# Netzteil-Regler.net
KiCad netlist of a schematic drawn in EAGLE
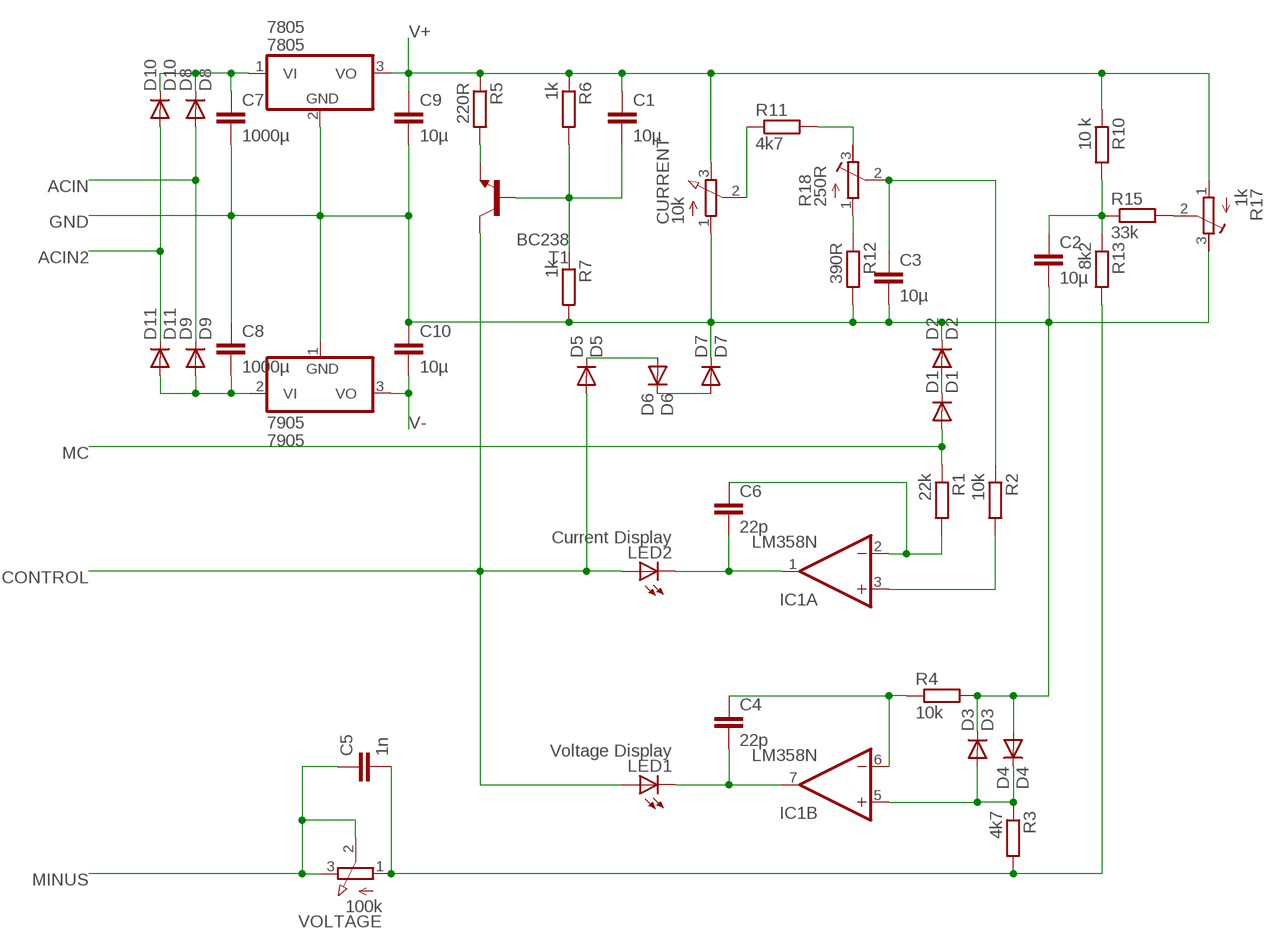
[diagram p0: schematic, sheet 1]

(export (version "E")
  (design (tool "Eeschema 10.0.6"))
  (components
    (comp (ref "7805")
      (value "7805")
      (footprint "eagle-import:TO220V")
      (libsource (lib "eagle-import") (part "78TV05"))
    )
    (comp (ref "7905")
      (value "7905")
      (footprint "eagle-import:TO220V")
      (libsource (lib "eagle-import") (part "MC79MT05C"))
    )
    (comp (ref "C1")
      (value "10µ")
      (footprint "eagle-import:C2.5-5")
      (libsource (lib "eagle-import") (part "C2.5/5"))
    )
    (comp (ref "C2")
      (value "10µ")
      (footprint "eagle-import:C2.5-5")
      (libsource (lib "eagle-import") (part "C2.5/5"))
    )
    (comp (ref "C3")
      (value "10µ")
      (footprint "eagle-import:C2.5-5")
      (libsource (lib "eagle-import") (part "C2.5/5"))
    )
    (comp (ref "C4")
      (value "22p")
      (footprint "eagle-import:C5B4.5")
      (libsource (lib "eagle-import") (part "C5/4.5"))
    )
    (comp (ref "C5")
      (value "1n")
      (footprint "eagle-import:C5B4.5")
      (libsource (lib "eagle-import") (part "C5/4.5"))
    )
    (comp (ref "C6")
      (value "22p")
      (footprint "eagle-import:C5B4.5")
      (libsource (lib "eagle-import") (part "C5/4.5"))
    )
    (comp (ref "C7")
      (value "1000µ")
      (footprint "eagle-import:C10B6")
      (libsource (lib "eagle-import") (part "C10/6"))
    )
    (comp (ref "C8")
      (value "1000µ")
      (footprint "eagle-import:C10B6")
      (libsource (lib "eagle-import") (part "C10/6"))
    )
    (comp (ref "C9")
      (value "10µ")
      (footprint "eagle-import:C2.5-5")
      (libsource (lib "eagle-import") (part "C2.5/5"))
    )
    (comp (ref "C10")
      (value "10µ")
      (footprint "eagle-import:C2.5-5")
      (libsource (lib "eagle-import") (part "C2.5/5"))
    )
    (comp (ref "CURRENT")
      (value "10k")
      (footprint "eagle-import:3RP_1610N")
      (libsource (lib "eagle-import") (part "3RP/1610N"))
    )
    (comp (ref "D1")
      (value "D1")
      (footprint "eagle-import:DO35-10")
      (libsource (lib "eagle-import") (part "1N4148DO35-10"))
    )
    (comp (ref "D2")
      (value "D2")
      (footprint "eagle-import:DO35-10")
      (libsource (lib "eagle-import") (part "1N4148DO35-10"))
    )
    (comp (ref "D3")
      (value "D3")
      (footprint "eagle-import:DO35-10")
      (libsource (lib "eagle-import") (part "1N4148DO35-10"))
    )
    (comp (ref "D4")
      (value "D4")
      (footprint "eagle-import:DO35-10")
      (libsource (lib "eagle-import") (part "1N4148DO35-10"))
    )
    (comp (ref "D5")
      (value "D5")
      (footprint "eagle-import:DO35-10")
      (libsource (lib "eagle-import") (part "1N4148DO35-10"))
    )
    (comp (ref "D6")
      (value "D6")
      (footprint "eagle-import:DO35-10")
      (libsource (lib "eagle-import") (part "1N4148DO35-10"))
    )
    (comp (ref "D7")
      (value "D7")
      (footprint "eagle-import:DO35-10")
      (libsource (lib "eagle-import") (part "1N4148DO35-10"))
    )
    (comp (ref "D8")
      (value "D8")
      (footprint "eagle-import:DO41-10")
      (libsource (lib "eagle-import") (part "1N4004"))
    )
    (comp (ref "D9")
      (value "D9")
      (footprint "eagle-import:DO41-10")
      (libsource (lib "eagle-import") (part "1N4004"))
    )
    (comp (ref "D10")
      (value "D10")
      (footprint "eagle-import:DO41-10")
      (libsource (lib "eagle-import") (part "1N4004"))
    )
    (comp (ref "D11")
      (value "D11")
      (footprint "eagle-import:DO41-10")
      (libsource (lib "eagle-import") (part "1N4004"))
    )
    (comp (ref "IC1")
      (value "LM358N")
      (footprint "eagle-import:DIL08")
      (libsource (lib "eagle-import") (part "LM358N"))
    )
    (comp (ref "LED1")
      (value "Voltage Display")
      (footprint "eagle-import:LED5MM")
      (libsource (lib "eagle-import") (part "LED5MM"))
    )
    (comp (ref "LED2")
      (value "Current Display")
      (footprint "eagle-import:LED5MM")
      (libsource (lib "eagle-import") (part "LED5MM"))
    )
    (comp (ref "R1")
      (value "22k")
      (footprint "eagle-import:0207_10")
      (libsource (lib "eagle-import") (part "R-EU_0207/10"))
    )
    (comp (ref "R2")
      (value "10k")
      (footprint "eagle-import:0207_10")
      (libsource (lib "eagle-import") (part "R-EU_0207/10"))
    )
    (comp (ref "R3")
      (value "4k7")
      (footprint "eagle-import:0207_10")
      (libsource (lib "eagle-import") (part "R-EU_0207/10"))
    )
    (comp (ref "R4")
      (value "10k")
      (footprint "eagle-import:0207_10")
      (libsource (lib "eagle-import") (part "R-EU_0207/10"))
    )
    (comp (ref "R5")
      (value "220R")
      (footprint "eagle-import:0207_10")
      (libsource (lib "eagle-import") (part "R-EU_0207/10"))
    )
    (comp (ref "R6")
      (value "1k")
      (footprint "eagle-import:0207_10")
      (libsource (lib "eagle-import") (part "R-EU_0207/10"))
    )
    (comp (ref "R7")
      (value "1k")
      (footprint "eagle-import:0207_10")
      (libsource (lib "eagle-import") (part "R-EU_0207/10"))
    )
    (comp (ref "R10")
      (value "10 k")
      (footprint "eagle-import:0207_10")
      (libsource (lib "eagle-import") (part "R-EU_0207/10"))
    )
    (comp (ref "R11")
      (value "4k7")
      (footprint "eagle-import:0207_10")
      (libsource (lib "eagle-import") (part "R-EU_0207/10"))
    )
    (comp (ref "R12")
      (value "390R")
      (footprint "eagle-import:0207_10")
      (libsource (lib "eagle-import") (part "R-EU_0207/10"))
    )
    (comp (ref "R13")
      (value "8k2")
      (footprint "eagle-import:0207_10")
      (libsource (lib "eagle-import") (part "R-EU_0207/10"))
    )
    (comp (ref "R15")
      (value "33k")
      (footprint "eagle-import:0207_10")
      (libsource (lib "eagle-import") (part "R-EU_0207/10"))
    )
    (comp (ref "R17")
      (value "1k")
      (footprint "eagle-import:RTRIM3296W")
      (libsource (lib "eagle-import") (part "R-TRIMM3296W"))
    )
    (comp (ref "R18")
      (value "250R")
      (footprint "eagle-import:RTRIM3296W")
      (libsource (lib "eagle-import") (part "R-TRIMM3296W"))
    )
    (comp (ref "T1")
      (value "BC238")
      (footprint "eagle-import:TO92-CBE")
      (libsource (lib "eagle-import") (part "-NPN-TO92-CBEBC238"))
    )
    (comp (ref "VOLTAGE")
      (value "100k")
      (footprint "eagle-import:3RP_1610N")
      (libsource (lib "eagle-import") (part "3RP/1610N"))
    )
  )
  (nets
    (net (code "1") (name "/ACIN") (class "Default")
      (node (ref "D8") (pin "A") (pinfunction "A_A") (pintype "passive"))
      (node (ref "D9") (pin "C") (pinfunction "C_C") (pintype "passive"))
    )
    (net (code "2") (name "/ACIN2") (class "Default")
      (node (ref "D10") (pin "A") (pinfunction "A_A") (pintype "passive"))
      (node (ref "D11") (pin "C") (pinfunction "C_C") (pintype "passive"))
    )
    (net (code "3") (name "/CONTROL") (class "Default")
      (node (ref "D5") (pin "A") (pinfunction "A_A") (pintype "passive"))
      (node (ref "LED1") (pin "A") (pinfunction "A_A") (pintype "passive"))
      (node (ref "LED2") (pin "A") (pinfunction "A_A") (pintype "passive"))
      (node (ref "T1") (pin "C") (pinfunction "C_C") (pintype "passive"))
    )
    (net (code "4") (name "/GND") (class "Default")
      (node (ref "7805") (pin "2") (pinfunction "GND_2") (pintype "passive"))
      (node (ref "7905") (pin "1") (pinfunction "GND_1") (pintype "passive"))
      (node (ref "C10") (pin "1") (pinfunction "1_1") (pintype "passive"))
      (node (ref "C2") (pin "2") (pinfunction "2_2") (pintype "passive"))
      (node (ref "C3") (pin "2") (pinfunction "2_2") (pintype "passive"))
      (node (ref "C7") (pin "2") (pinfunction "2_2") (pintype "passive"))
      (node (ref "C8") (pin "1") (pinfunction "1_1") (pintype "passive"))
      (node (ref "C9") (pin "2") (pinfunction "2_2") (pintype "passive"))
      (node (ref "CURRENT") (pin "1") (pinfunction "A_1") (pintype "passive"))
      (node (ref "D2") (pin "C") (pinfunction "C_C") (pintype "passive"))
      (node (ref "D3") (pin "C") (pinfunction "C_C") (pintype "passive"))
      (node (ref "D4") (pin "A") (pinfunction "A_A") (pintype "passive"))
      (node (ref "D7") (pin "C") (pinfunction "C_C") (pintype "passive"))
      (node (ref "R12") (pin "2") (pinfunction "2_2") (pintype "passive"))
      (node (ref "R17") (pin "3") (pinfunction "A_3") (pintype "passive"))
      (node (ref "R4") (pin "2") (pinfunction "2_2") (pintype "passive"))
      (node (ref "R7") (pin "2") (pinfunction "2_2") (pintype "passive"))
    )
    (net (code "5") (name "/MC") (class "Default")
      (node (ref "D1") (pin "A") (pinfunction "A_A") (pintype "passive"))
      (node (ref "R1") (pin "1") (pinfunction "1_1") (pintype "passive"))
    )
    (net (code "6") (name "/MINUS") (class "Default")
      (node (ref "C5") (pin "1") (pinfunction "1_1") (pintype "passive"))
      (node (ref "VOLTAGE") (pin "2") (pinfunction "S_2") (pintype "passive"))
      (node (ref "VOLTAGE") (pin "3") (pinfunction "E_3") (pintype "passive"))
    )
    (net (code "7") (name "/V+") (class "Default")
      (node (ref "7805") (pin "3") (pinfunction "VO_3") (pintype "passive"))
      (node (ref "C1") (pin "1") (pinfunction "1_1") (pintype "passive"))
      (node (ref "C9") (pin "1") (pinfunction "1_1") (pintype "passive"))
      (node (ref "CURRENT") (pin "3") (pinfunction "E_3") (pintype "passive"))
      (node (ref "R10") (pin "1") (pinfunction "1_1") (pintype "passive"))
      (node (ref "R17") (pin "1") (pinfunction "E_1") (pintype "passive"))
      (node (ref "R5") (pin "1") (pinfunction "1_1") (pintype "passive"))
      (node (ref "R6") (pin "1") (pinfunction "1_1") (pintype "passive"))
    )
    (net (code "8") (name "/V-") (class "Default")
      (node (ref "7905") (pin "3") (pinfunction "VO_3") (pintype "passive"))
      (node (ref "C10") (pin "2") (pinfunction "2_2") (pintype "passive"))
    )
    (net (code "9") (name "Net-(7805-VI)") (class "Default")
      (node (ref "7805") (pin "1") (pinfunction "VI_1") (pintype "input"))
      (node (ref "C7") (pin "1") (pinfunction "1_1") (pintype "passive"))
      (node (ref "D10") (pin "C") (pinfunction "C_C") (pintype "passive"))
      (node (ref "D8") (pin "C") (pinfunction "C_C") (pintype "passive"))
    )
    (net (code "10") (name "Net-(7905-VI)") (class "Default")
      (node (ref "7905") (pin "2") (pinfunction "VI_2") (pintype "input"))
      (node (ref "C8") (pin "2") (pinfunction "2_2") (pintype "passive"))
      (node (ref "D11") (pin "A") (pinfunction "A_A") (pintype "passive"))
      (node (ref "D9") (pin "A") (pinfunction "A_A") (pintype "passive"))
    )
    (net (code "11") (name "Net-(C1-Pad2)") (class "Default")
      (node (ref "C1") (pin "2") (pinfunction "2_2") (pintype "passive"))
      (node (ref "R6") (pin "2") (pinfunction "2_2") (pintype "passive"))
      (node (ref "R7") (pin "1") (pinfunction "1_1") (pintype "passive"))
      (node (ref "T1") (pin "B") (pinfunction "B_B") (pintype "passive"))
    )
    (net (code "12") (name "Net-(C2-Pad1)") (class "Default")
      (node (ref "C2") (pin "1") (pinfunction "1_1") (pintype "passive"))
      (node (ref "R10") (pin "2") (pinfunction "2_2") (pintype "passive"))
      (node (ref "R13") (pin "1") (pinfunction "1_1") (pintype "passive"))
      (node (ref "R15") (pin "1") (pinfunction "1_1") (pintype "passive"))
    )
    (net (code "13") (name "Net-(CURRENT-S)") (class "Default")
      (node (ref "CURRENT") (pin "2") (pinfunction "S_2") (pintype "passive"))
      (node (ref "R11") (pin "1") (pinfunction "1_1") (pintype "passive"))
    )
    (net (code "14") (name "Net-(D1-PadC)") (class "Default")
      (node (ref "D1") (pin "C") (pinfunction "C_C") (pintype "passive"))
      (node (ref "D2") (pin "A") (pinfunction "A_A") (pintype "passive"))
    )
    (net (code "15") (name "Net-(D5-PadC)") (class "Default")
      (node (ref "D5") (pin "C") (pinfunction "C_C") (pintype "passive"))
      (node (ref "D6") (pin "A") (pinfunction "A_A") (pintype "passive"))
    )
    (net (code "16") (name "Net-(D6-PadC)") (class "Default")
      (node (ref "D6") (pin "C") (pinfunction "C_C") (pintype "passive"))
      (node (ref "D7") (pin "A") (pinfunction "A_A") (pintype "passive"))
    )
    (net (code "17") (name "Net-(IC1A-+IN)") (class "Default")
      (node (ref "IC1") (pin "3") (pinfunction "+IN_3") (pintype "input"))
      (node (ref "R2") (pin "2") (pinfunction "2_2") (pintype "passive"))
    )
    (net (code "18") (name "Net-(IC1A--IN)") (class "Default")
      (node (ref "C6") (pin "1") (pinfunction "1_1") (pintype "passive"))
      (node (ref "IC1") (pin "2") (pinfunction "-IN_2") (pintype "input"))
      (node (ref "R1") (pin "2") (pinfunction "2_2") (pintype "passive"))
    )
    (net (code "19") (name "Net-(IC1A-OUT)") (class "Default")
      (node (ref "C6") (pin "2") (pinfunction "2_2") (pintype "passive"))
      (node (ref "IC1") (pin "1") (pinfunction "OUT_1") (pintype "output"))
      (node (ref "LED2") (pin "K") (pinfunction "C_K") (pintype "passive"))
    )
    (net (code "20") (name "Net-(IC1B-+IN)") (class "Default")
      (node (ref "D3") (pin "A") (pinfunction "A_A") (pintype "passive"))
      (node (ref "D4") (pin "C") (pinfunction "C_C") (pintype "passive"))
      (node (ref "IC1") (pin "5") (pinfunction "+IN_5") (pintype "input"))
      (node (ref "R3") (pin "1") (pinfunction "1_1") (pintype "passive"))
    )
    (net (code "21") (name "Net-(IC1B--IN)") (class "Default")
      (node (ref "C4") (pin "1") (pinfunction "1_1") (pintype "passive"))
      (node (ref "IC1") (pin "6") (pinfunction "-IN_6") (pintype "input"))
      (node (ref "R4") (pin "1") (pinfunction "1_1") (pintype "passive"))
    )
    (net (code "22") (name "Net-(IC1B-OUT)") (class "Default")
      (node (ref "C4") (pin "2") (pinfunction "2_2") (pintype "passive"))
      (node (ref "IC1") (pin "7") (pinfunction "OUT_7") (pintype "output"))
      (node (ref "LED1") (pin "K") (pinfunction "C_K") (pintype "passive"))
    )
    (net (code "23") (name "Net-(R5-Pad2)") (class "Default")
      (node (ref "R5") (pin "2") (pinfunction "2_2") (pintype "passive"))
      (node (ref "T1") (pin "E") (pinfunction "E_E") (pintype "passive"))
    )
    (net (code "24") (name "Net-(R17-S)") (class "Default")
      (node (ref "R15") (pin "2") (pinfunction "2_2") (pintype "passive"))
      (node (ref "R17") (pin "2") (pinfunction "S_2") (pintype "passive"))
    )
    (net (code "25") (name "Net-(R18-A)") (class "Default")
      (node (ref "R11") (pin "2") (pinfunction "2_2") (pintype "passive"))
      (node (ref "R18") (pin "3") (pinfunction "A_3") (pintype "passive"))
    )
    (net (code "26") (name "Net-(R18-E)") (class "Default")
      (node (ref "R12") (pin "1") (pinfunction "1_1") (pintype "passive"))
      (node (ref "R18") (pin "1") (pinfunction "E_1") (pintype "passive"))
    )
    (net (code "27") (name "Net-(R18-S)") (class "Default")
      (node (ref "C3") (pin "1") (pinfunction "1_1") (pintype "passive"))
      (node (ref "R18") (pin "2") (pinfunction "S_2") (pintype "passive"))
      (node (ref "R2") (pin "1") (pinfunction "1_1") (pintype "passive"))
    )
    (net (code "28") (name "Net-(VOLTAGE-A)") (class "Default")
      (node (ref "C5") (pin "2") (pinfunction "2_2") (pintype "passive"))
      (node (ref "R13") (pin "2") (pinfunction "2_2") (pintype "passive"))
      (node (ref "R3") (pin "2") (pinfunction "2_2") (pintype "passive"))
      (node (ref "VOLTAGE") (pin "1") (pinfunction "A_1") (pintype "passive"))
    )
  )
)
